# M2_KEY_M.net
KiCad netlist of a schematic drawn in Altium Designer
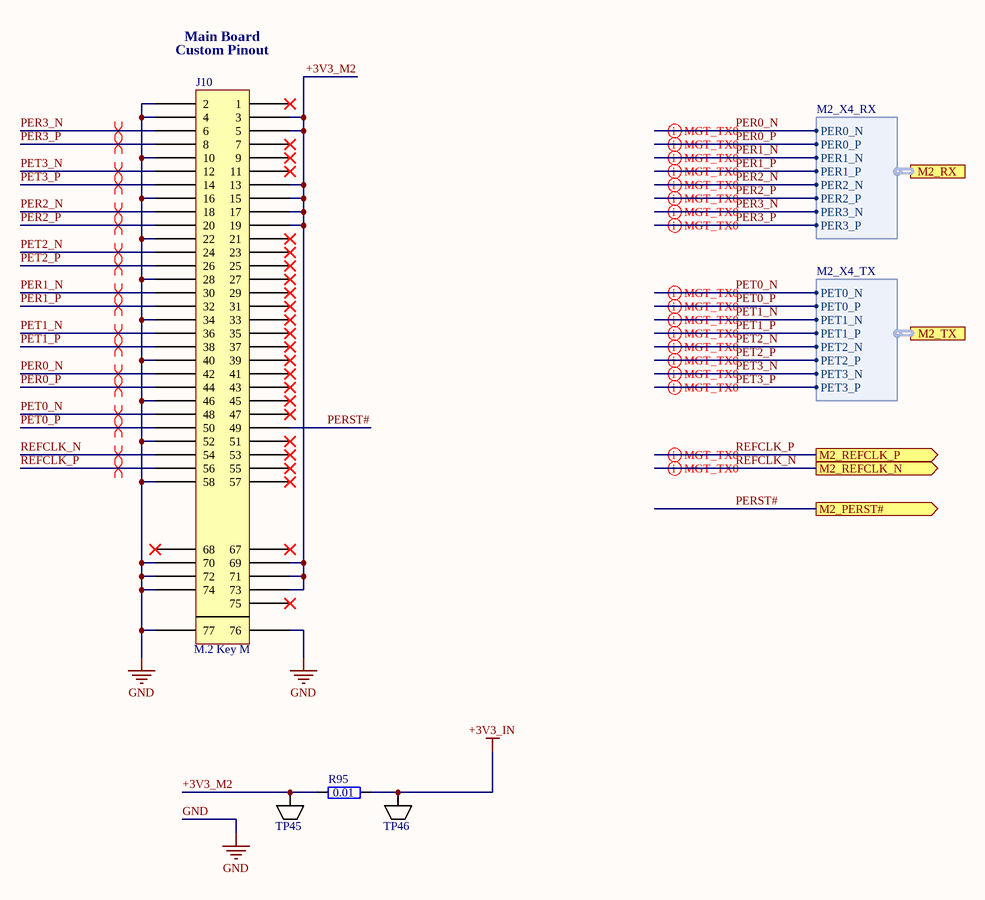
[diagram p0: M2_KEY_M.SchDoc]

(export (version "E")
  (design (tool "Eeschema 10.0.6"))
  (components
    (comp (ref "J10")
      (value "M.2 Key M")
      (footprint "TE_M2_KEYM_2199230")
      (fields
        (field (name "MANUFACTURER") "TE Connectivity")
        (field (name "MANUFACTURER PART NUMBER") "1-2199230-5")
      )
      (libsource (lib "DSO") (part "CONN M.2 Key M FEMALE"))
    )
    (comp (ref "R95")
      (value "0.01")
      (footprint "GEN_R_0603")
      (fields
        (field (name "TOLERANCE") "1%")
        (field (name "HOUSE PART NUMBER") "R-0.01-0603-1%-001")
        (field (name "MANUFACTURER") "Susumu")
      )
      (libsource (lib "DSO") (part "RES 0.01 OHM 1% 1/4W 0603"))
    )
    (comp (ref "TP45")
      (value "5015")
      (footprint "KEY_5015")
      (fields (field (name "MANUFACTURER") "Keystone Electronics"))
      (libsource (lib "DSO") (part "TP KEYSTONE 5015"))
    )
    (comp (ref "TP46")
      (value "5015")
      (footprint "KEY_5015")
      (fields (field (name "MANUFACTURER") "Keystone Electronics"))
      (libsource (lib "DSO") (part "TP KEYSTONE 5015"))
    )
  )
  (nets
    (net (code "3") (name "+3V3_IN") (class "Default")
      (node (ref "R95") (pin "2") (pinfunction "2_2") (pintype "passive"))
      (node (ref "TP46") (pin "1") (pinfunction "1_1") (pintype "passive"))
    )
    (net (code "4") (name "/+3V3_M2") (class "Default")
      (node (ref "J10") (pin "13") (pinfunction "13_13") (pintype "passive"))
      (node (ref "J10") (pin "15") (pinfunction "15_15") (pintype "passive"))
      (node (ref "J10") (pin "17") (pinfunction "17_17") (pintype "passive"))
      (node (ref "J10") (pin "19") (pinfunction "19_19") (pintype "passive"))
      (node (ref "J10") (pin "3") (pinfunction "3_3") (pintype "passive"))
      (node (ref "J10") (pin "5") (pinfunction "5_5") (pintype "passive"))
      (node (ref "J10") (pin "69") (pinfunction "69_69") (pintype "passive"))
      (node (ref "J10") (pin "71") (pinfunction "71_71") (pintype "passive"))
      (node (ref "J10") (pin "73") (pinfunction "73_73") (pintype "passive"))
      (node (ref "R95") (pin "1") (pinfunction "1_1") (pintype "passive"))
      (node (ref "TP45") (pin "1") (pinfunction "1_1") (pintype "passive"))
    )
    (net (code "5") (name "/PER0_N") (class "Default")
      (node (ref "J10") (pin "42") (pinfunction "42_42") (pintype "passive"))
    )
    (net (code "6") (name "/PER0_P") (class "Default")
      (node (ref "J10") (pin "44") (pinfunction "44_44") (pintype "passive"))
    )
    (net (code "7") (name "/PER1_N") (class "Default")
      (node (ref "J10") (pin "30") (pinfunction "30_30") (pintype "passive"))
    )
    (net (code "8") (name "/PER1_P") (class "Default")
      (node (ref "J10") (pin "32") (pinfunction "32_32") (pintype "passive"))
    )
    (net (code "9") (name "/PER2_N") (class "Default")
      (node (ref "J10") (pin "18") (pinfunction "18_18") (pintype "passive"))
    )
    (net (code "10") (name "/PER2_P") (class "Default")
      (node (ref "J10") (pin "20") (pinfunction "20_20") (pintype "passive"))
    )
    (net (code "11") (name "/PER3_N") (class "Default")
      (node (ref "J10") (pin "6") (pinfunction "6_6") (pintype "passive"))
    )
    (net (code "12") (name "/PER3_P") (class "Default")
      (node (ref "J10") (pin "8") (pinfunction "8_8") (pintype "passive"))
    )
    (net (code "13") (name "/PERST#") (class "Default")
      (node (ref "J10") (pin "49") (pinfunction "49_49") (pintype "passive"))
    )
    (net (code "14") (name "/PET0_N") (class "Default")
      (node (ref "J10") (pin "48") (pinfunction "48_48") (pintype "passive"))
    )
    (net (code "15") (name "/PET0_P") (class "Default")
      (node (ref "J10") (pin "50") (pinfunction "50_50") (pintype "passive"))
    )
    (net (code "16") (name "/PET1_N") (class "Default")
      (node (ref "J10") (pin "36") (pinfunction "36_36") (pintype "passive"))
    )
    (net (code "17") (name "/PET1_P") (class "Default")
      (node (ref "J10") (pin "38") (pinfunction "38_38") (pintype "passive"))
    )
    (net (code "18") (name "/PET2_N") (class "Default")
      (node (ref "J10") (pin "24") (pinfunction "24_24") (pintype "passive"))
    )
    (net (code "19") (name "/PET2_P") (class "Default")
      (node (ref "J10") (pin "26") (pinfunction "26_26") (pintype "passive"))
    )
    (net (code "20") (name "/PET3_N") (class "Default")
      (node (ref "J10") (pin "12") (pinfunction "12_12") (pintype "passive"))
    )
    (net (code "21") (name "/PET3_P") (class "Default")
      (node (ref "J10") (pin "14") (pinfunction "14_14") (pintype "passive"))
    )
    (net (code "22") (name "/REFCLK_N") (class "Default")
      (node (ref "J10") (pin "54") (pinfunction "54_54") (pintype "passive"))
    )
    (net (code "23") (name "/REFCLK_P") (class "Default")
      (node (ref "J10") (pin "56") (pinfunction "56_56") (pintype "passive"))
    )
    (net (code "26") (name "GND") (class "Default")
      (node (ref "J10") (pin "10") (pinfunction "10_10") (pintype "passive"))
      (node (ref "J10") (pin "16") (pinfunction "16_16") (pintype "passive"))
      (node (ref "J10") (pin "2") (pinfunction "2_2") (pintype "passive"))
      (node (ref "J10") (pin "22") (pinfunction "22_22") (pintype "passive"))
      (node (ref "J10") (pin "28") (pinfunction "28_28") (pintype "passive"))
      (node (ref "J10") (pin "34") (pinfunction "34_34") (pintype "passive"))
      (node (ref "J10") (pin "4") (pinfunction "4_4") (pintype "passive"))
      (node (ref "J10") (pin "40") (pinfunction "40_40") (pintype "passive"))
      (node (ref "J10") (pin "46") (pinfunction "46_46") (pintype "passive"))
      (node (ref "J10") (pin "52") (pinfunction "52_52") (pintype "passive"))
      (node (ref "J10") (pin "58") (pinfunction "58_58") (pintype "passive"))
      (node (ref "J10") (pin "70") (pinfunction "70_70") (pintype "passive"))
      (node (ref "J10") (pin "72") (pinfunction "72_72") (pintype "passive"))
      (node (ref "J10") (pin "74") (pinfunction "74_74") (pintype "passive"))
      (node (ref "J10") (pin "76") (pinfunction "76_76") (pintype "passive"))
      (node (ref "J10") (pin "77") (pinfunction "77_77") (pintype "passive"))
    )
    (net (code "27") (name "unconnected-(J10-Pad1)") (class "Default")
      (node (ref "J10") (pin "1") (pinfunction "1_1") (pintype "passive+no_connect"))
    )
    (net (code "28") (name "unconnected-(J10-Pad7)") (class "Default")
      (node (ref "J10") (pin "7") (pinfunction "7_7") (pintype "passive+no_connect"))
    )
    (net (code "29") (name "unconnected-(J10-Pad9)") (class "Default")
      (node (ref "J10") (pin "9") (pinfunction "9_9") (pintype "passive+no_connect"))
    )
    (net (code "30") (name "unconnected-(J10-Pad11)") (class "Default")
      (node (ref "J10") (pin "11") (pinfunction "11_11") (pintype "passive+no_connect"))
    )
    (net (code "31") (name "unconnected-(J10-Pad21)") (class "Default")
      (node (ref "J10") (pin "21") (pinfunction "21_21") (pintype "passive+no_connect"))
    )
    (net (code "32") (name "unconnected-(J10-Pad23)") (class "Default")
      (node (ref "J10") (pin "23") (pinfunction "23_23") (pintype "passive+no_connect"))
    )
    (net (code "33") (name "unconnected-(J10-Pad25)") (class "Default")
      (node (ref "J10") (pin "25") (pinfunction "25_25") (pintype "passive+no_connect"))
    )
    (net (code "34") (name "unconnected-(J10-Pad27)") (class "Default")
      (node (ref "J10") (pin "27") (pinfunction "27_27") (pintype "passive+no_connect"))
    )
    (net (code "35") (name "unconnected-(J10-Pad29)") (class "Default")
      (node (ref "J10") (pin "29") (pinfunction "29_29") (pintype "passive+no_connect"))
    )
    (net (code "36") (name "unconnected-(J10-Pad31)") (class "Default")
      (node (ref "J10") (pin "31") (pinfunction "31_31") (pintype "passive+no_connect"))
    )
    (net (code "37") (name "unconnected-(J10-Pad33)") (class "Default")
      (node (ref "J10") (pin "33") (pinfunction "33_33") (pintype "passive+no_connect"))
    )
    (net (code "38") (name "unconnected-(J10-Pad35)") (class "Default")
      (node (ref "J10") (pin "35") (pinfunction "35_35") (pintype "passive+no_connect"))
    )
    (net (code "39") (name "unconnected-(J10-Pad37)") (class "Default")
      (node (ref "J10") (pin "37") (pinfunction "37_37") (pintype "passive+no_connect"))
    )
    (net (code "40") (name "unconnected-(J10-Pad39)") (class "Default")
      (node (ref "J10") (pin "39") (pinfunction "39_39") (pintype "passive+no_connect"))
    )
    (net (code "41") (name "unconnected-(J10-Pad41)") (class "Default")
      (node (ref "J10") (pin "41") (pinfunction "41_41") (pintype "passive+no_connect"))
    )
    (net (code "42") (name "unconnected-(J10-Pad43)") (class "Default")
      (node (ref "J10") (pin "43") (pinfunction "43_43") (pintype "passive+no_connect"))
    )
    (net (code "43") (name "unconnected-(J10-Pad45)") (class "Default")
      (node (ref "J10") (pin "45") (pinfunction "45_45") (pintype "passive+no_connect"))
    )
    (net (code "44") (name "unconnected-(J10-Pad47)") (class "Default")
      (node (ref "J10") (pin "47") (pinfunction "47_47") (pintype "passive+no_connect"))
    )
    (net (code "45") (name "unconnected-(J10-Pad51)") (class "Default")
      (node (ref "J10") (pin "51") (pinfunction "51_51") (pintype "passive+no_connect"))
    )
    (net (code "46") (name "unconnected-(J10-Pad53)") (class "Default")
      (node (ref "J10") (pin "53") (pinfunction "53_53") (pintype "passive+no_connect"))
    )
    (net (code "47") (name "unconnected-(J10-Pad55)") (class "Default")
      (node (ref "J10") (pin "55") (pinfunction "55_55") (pintype "passive+no_connect"))
    )
    (net (code "48") (name "unconnected-(J10-Pad57)") (class "Default")
      (node (ref "J10") (pin "57") (pinfunction "57_57") (pintype "passive+no_connect"))
    )
    (net (code "49") (name "unconnected-(J10-Pad67)") (class "Default")
      (node (ref "J10") (pin "67") (pinfunction "67_67") (pintype "passive+no_connect"))
    )
    (net (code "50") (name "unconnected-(J10-Pad68)") (class "Default")
      (node (ref "J10") (pin "68") (pinfunction "68_68") (pintype "passive+no_connect"))
    )
    (net (code "51") (name "unconnected-(J10-Pad75)") (class "Default")
      (node (ref "J10") (pin "75") (pinfunction "75_75") (pintype "passive+no_connect"))
    )
  )
)
